# 6-BOOT_SELECT.net
KiCad netlist of a schematic drawn in Altium Designer
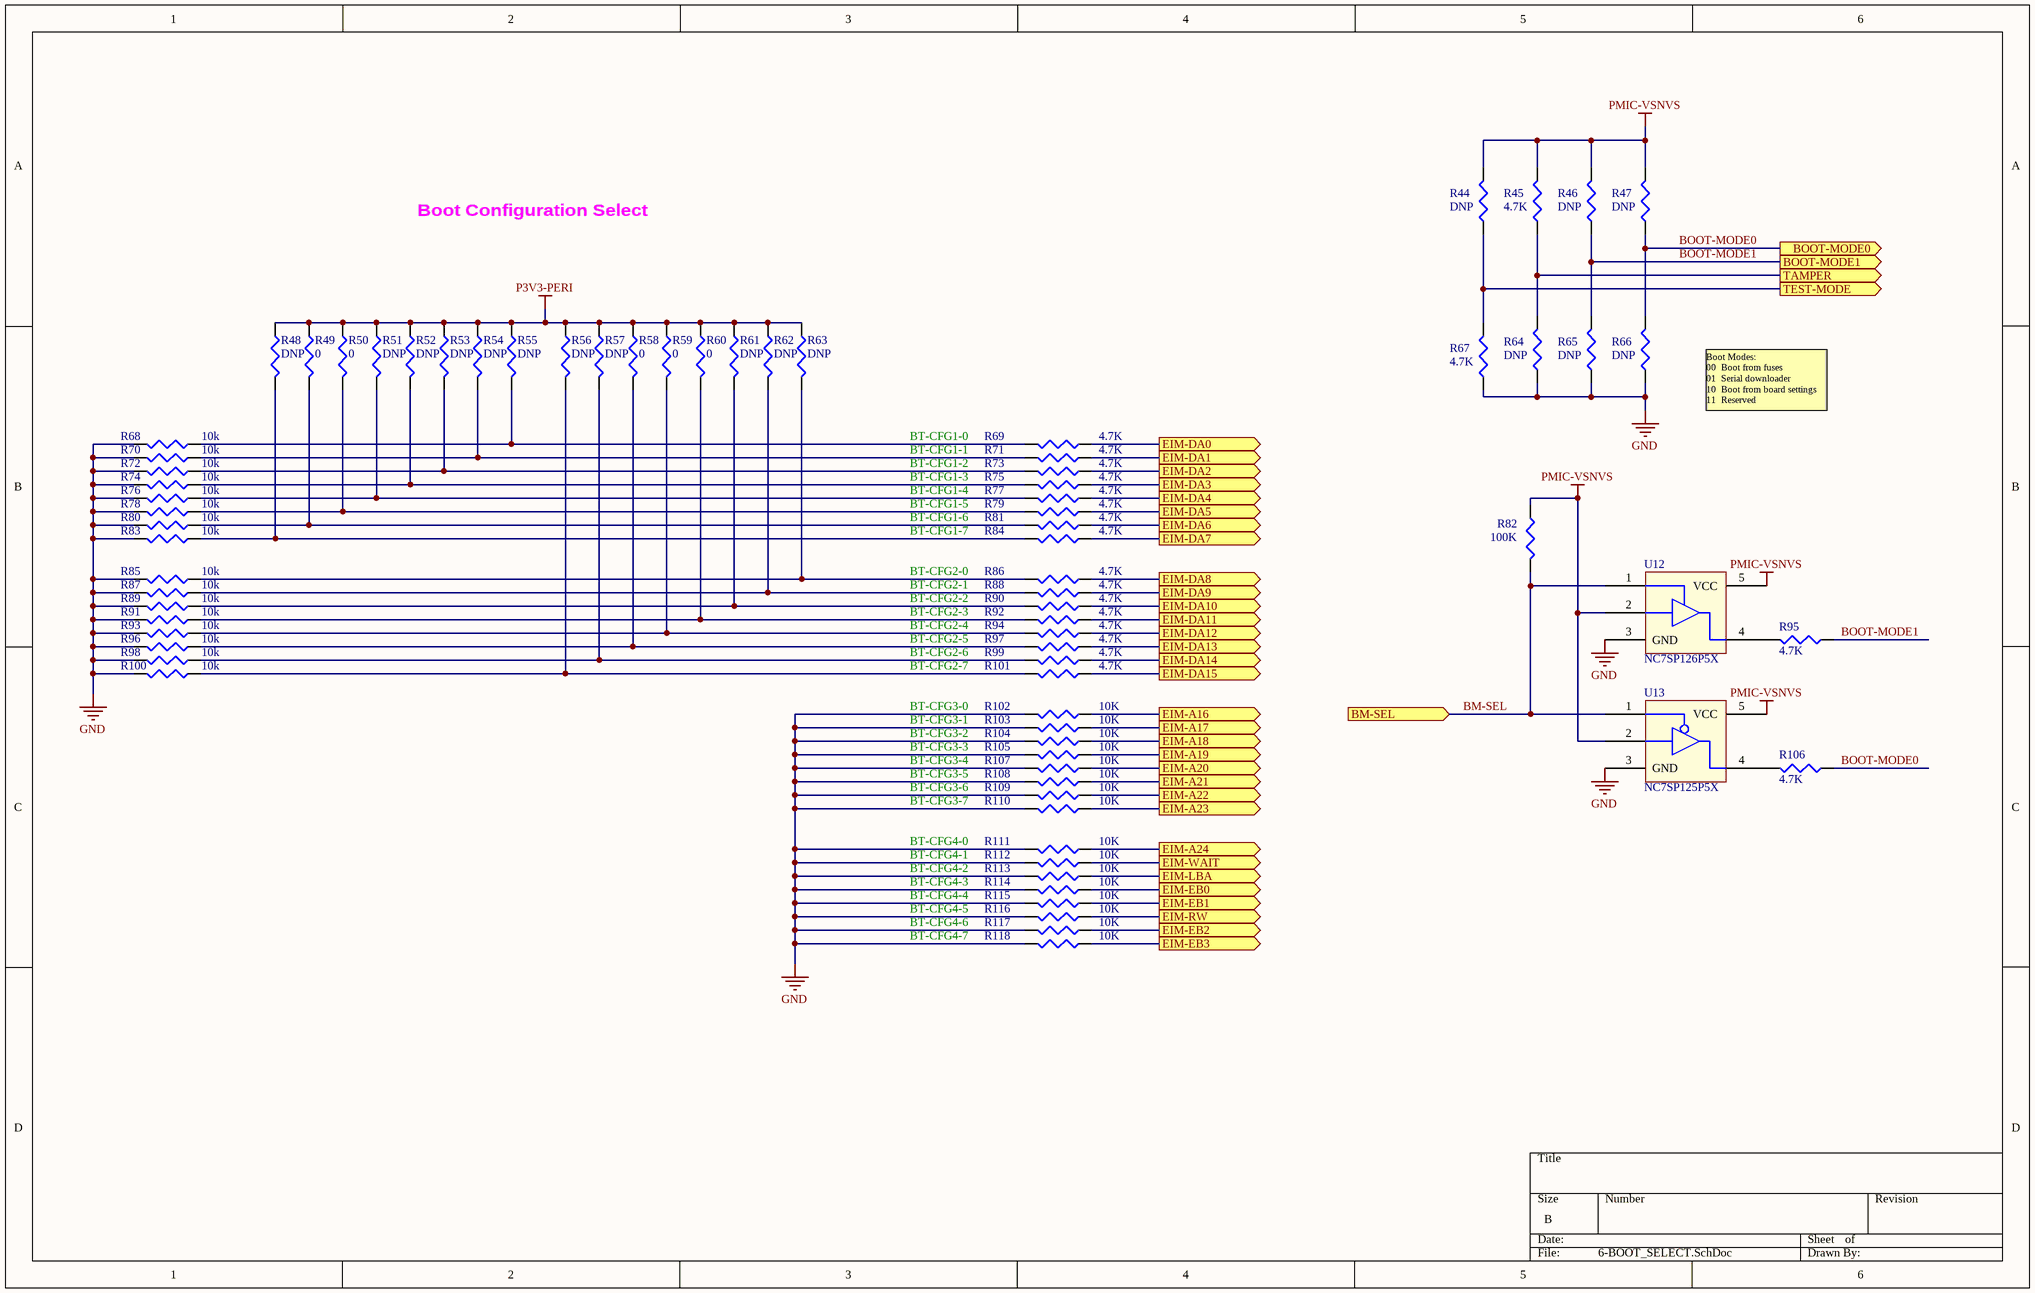
[diagram p0: 6-BOOT_SELECT.SchDoc]

(export (version "E")
  (design (tool "Eeschema 10.0.6"))
  (components
    (comp (ref "R44")
      (value "DNP")
      (footprint "0402_CC")
      (description "Resistor")
      (fields (field (name "PUBLISHER") "Altium Limited"))
      (libsource (lib "Miscellaneous Devices") (part "Res3"))
    )
    (comp (ref "R45")
      (value "4.7K")
      (footprint "0402_CC")
      (description "Resistor")
      (fields (field (name "PUBLISHER") "Altium Limited"))
      (libsource (lib "Miscellaneous Devices") (part "Res3"))
    )
    (comp (ref "R46")
      (value "DNP")
      (footprint "0402_CC")
      (description "Resistor")
      (fields (field (name "PUBLISHER") "Altium Limited"))
      (libsource (lib "Miscellaneous Devices") (part "Res3"))
    )
    (comp (ref "R47")
      (value "DNP")
      (footprint "0402_CC")
      (description "Resistor")
      (fields (field (name "PUBLISHER") "Altium Limited"))
      (libsource (lib "Miscellaneous Devices") (part "Res3"))
    )
    (comp (ref "R48")
      (value "DNP")
      (footprint "0402_CC")
      (description "Resistor")
      (fields (field (name "PUBLISHER") "Altium Limited"))
      (libsource (lib "Miscellaneous Devices") (part "Res3"))
    )
    (comp (ref "R49")
      (value "0")
      (footprint "0402_CC")
      (description "Resistor")
      (fields (field (name "PUBLISHER") "Altium Limited"))
      (libsource (lib "Miscellaneous Devices") (part "Res3"))
    )
    (comp (ref "R50")
      (value "0")
      (footprint "0402_CC")
      (description "Resistor")
      (fields (field (name "PUBLISHER") "Altium Limited"))
      (libsource (lib "Miscellaneous Devices") (part "Res3"))
    )
    (comp (ref "R51")
      (value "DNP")
      (footprint "0402_CC")
      (description "Resistor")
      (fields (field (name "PUBLISHER") "Altium Limited"))
      (libsource (lib "Miscellaneous Devices") (part "Res3"))
    )
    (comp (ref "R52")
      (value "DNP")
      (footprint "0402_CC")
      (description "Resistor")
      (fields (field (name "PUBLISHER") "Altium Limited"))
      (libsource (lib "Miscellaneous Devices") (part "Res3"))
    )
    (comp (ref "R53")
      (value "DNP")
      (footprint "0402_CC")
      (description "Resistor")
      (fields (field (name "PUBLISHER") "Altium Limited"))
      (libsource (lib "Miscellaneous Devices") (part "Res3"))
    )
    (comp (ref "R54")
      (value "DNP")
      (footprint "0402_CC")
      (description "Resistor")
      (fields (field (name "PUBLISHER") "Altium Limited"))
      (libsource (lib "Miscellaneous Devices") (part "Res3"))
    )
    (comp (ref "R55")
      (value "DNP")
      (footprint "0402_CC")
      (description "Resistor")
      (fields (field (name "PUBLISHER") "Altium Limited"))
      (libsource (lib "Miscellaneous Devices") (part "Res3"))
    )
    (comp (ref "R56")
      (value "DNP")
      (footprint "0402_CC")
      (description "Resistor")
      (fields (field (name "PUBLISHER") "Altium Limited"))
      (libsource (lib "Miscellaneous Devices") (part "Res3"))
    )
    (comp (ref "R57")
      (value "DNP")
      (footprint "0402_CC")
      (description "Resistor")
      (fields (field (name "PUBLISHER") "Altium Limited"))
      (libsource (lib "Miscellaneous Devices") (part "Res3"))
    )
    (comp (ref "R58")
      (value "0")
      (footprint "0402_CC")
      (description "Resistor")
      (fields (field (name "PUBLISHER") "Altium Limited"))
      (libsource (lib "Miscellaneous Devices") (part "Res3"))
    )
    (comp (ref "R59")
      (value "0")
      (footprint "0402_CC")
      (description "Resistor")
      (fields (field (name "PUBLISHER") "Altium Limited"))
      (libsource (lib "Miscellaneous Devices") (part "Res3"))
    )
    (comp (ref "R60")
      (value "0")
      (footprint "0402_CC")
      (description "Resistor")
      (fields (field (name "PUBLISHER") "Altium Limited"))
      (libsource (lib "Miscellaneous Devices") (part "Res3"))
    )
    (comp (ref "R61")
      (value "DNP")
      (footprint "0402_CC")
      (description "Resistor")
      (fields (field (name "PUBLISHER") "Altium Limited"))
      (libsource (lib "Miscellaneous Devices") (part "Res3"))
    )
    (comp (ref "R62")
      (value "DNP")
      (footprint "0402_CC")
      (description "Resistor")
      (fields (field (name "PUBLISHER") "Altium Limited"))
      (libsource (lib "Miscellaneous Devices") (part "Res3"))
    )
    (comp (ref "R63")
      (value "DNP")
      (footprint "0402_CC")
      (description "Resistor")
      (fields (field (name "PUBLISHER") "Altium Limited"))
      (libsource (lib "Miscellaneous Devices") (part "Res3"))
    )
    (comp (ref "R64")
      (value "DNP")
      (footprint "0402_CC")
      (description "Resistor")
      (fields (field (name "PUBLISHER") "Altium Limited"))
      (libsource (lib "Miscellaneous Devices") (part "Res3"))
    )
    (comp (ref "R65")
      (value "DNP")
      (footprint "0402_CC")
      (description "Resistor")
      (fields (field (name "PUBLISHER") "Altium Limited"))
      (libsource (lib "Miscellaneous Devices") (part "Res3"))
    )
    (comp (ref "R66")
      (value "DNP")
      (footprint "0402_CC")
      (description "Resistor")
      (fields (field (name "PUBLISHER") "Altium Limited"))
      (libsource (lib "Miscellaneous Devices") (part "Res3"))
    )
    (comp (ref "R67")
      (value "4.7K")
      (footprint "0402_CC")
      (description "Resistor")
      (fields (field (name "PUBLISHER") "Altium Limited"))
      (libsource (lib "Miscellaneous Devices") (part "Res3"))
    )
    (comp (ref "R68")
      (value "10k")
      (footprint "0402_CC")
      (description "Resistor")
      (fields (field (name "PUBLISHER") "Altium Limited"))
      (libsource (lib "Miscellaneous Devices") (part "Res3"))
    )
    (comp (ref "R69")
      (value "4.7K")
      (footprint "0402_CC")
      (description "Resistor")
      (fields (field (name "PUBLISHER") "Altium Limited"))
      (libsource (lib "Miscellaneous Devices") (part "Res3"))
    )
    (comp (ref "R70")
      (value "10k")
      (footprint "0402_CC")
      (description "Resistor")
      (fields (field (name "PUBLISHER") "Altium Limited"))
      (libsource (lib "Miscellaneous Devices") (part "Res3"))
    )
    (comp (ref "R71")
      (value "4.7K")
      (footprint "0402_CC")
      (description "Resistor")
      (fields (field (name "PUBLISHER") "Altium Limited"))
      (libsource (lib "Miscellaneous Devices") (part "Res3"))
    )
    (comp (ref "R72")
      (value "10k")
      (footprint "0402_CC")
      (description "Resistor")
      (fields (field (name "PUBLISHER") "Altium Limited"))
      (libsource (lib "Miscellaneous Devices") (part "Res3"))
    )
    (comp (ref "R73")
      (value "4.7K")
      (footprint "0402_CC")
      (description "Resistor")
      (fields (field (name "PUBLISHER") "Altium Limited"))
      (libsource (lib "Miscellaneous Devices") (part "Res3"))
    )
    (comp (ref "R74")
      (value "10k")
      (footprint "0402_CC")
      (description "Resistor")
      (fields (field (name "PUBLISHER") "Altium Limited"))
      (libsource (lib "Miscellaneous Devices") (part "Res3"))
    )
    (comp (ref "R75")
      (value "4.7K")
      (footprint "0402_CC")
      (description "Resistor")
      (fields (field (name "PUBLISHER") "Altium Limited"))
      (libsource (lib "Miscellaneous Devices") (part "Res3"))
    )
    (comp (ref "R76")
      (value "10k")
      (footprint "0402_CC")
      (description "Resistor")
      (fields (field (name "PUBLISHER") "Altium Limited"))
      (libsource (lib "Miscellaneous Devices") (part "Res3"))
    )
    (comp (ref "R77")
      (value "4.7K")
      (footprint "0402_CC")
      (description "Resistor")
      (fields (field (name "PUBLISHER") "Altium Limited"))
      (libsource (lib "Miscellaneous Devices") (part "Res3"))
    )
    (comp (ref "R78")
      (value "10k")
      (footprint "0402_CC")
      (description "Resistor")
      (fields (field (name "PUBLISHER") "Altium Limited"))
      (libsource (lib "Miscellaneous Devices") (part "Res3"))
    )
    (comp (ref "R79")
      (value "4.7K")
      (footprint "0402_CC")
      (description "Resistor")
      (fields (field (name "PUBLISHER") "Altium Limited"))
      (libsource (lib "Miscellaneous Devices") (part "Res3"))
    )
    (comp (ref "R80")
      (value "10k")
      (footprint "0402_CC")
      (description "Resistor")
      (fields (field (name "PUBLISHER") "Altium Limited"))
      (libsource (lib "Miscellaneous Devices") (part "Res3"))
    )
    (comp (ref "R81")
      (value "4.7K")
      (footprint "0402_CC")
      (description "Resistor")
      (fields (field (name "PUBLISHER") "Altium Limited"))
      (libsource (lib "Miscellaneous Devices") (part "Res3"))
    )
    (comp (ref "R82")
      (value "100K")
      (footprint "0402_CC")
      (description "Resistor")
      (fields (field (name "PUBLISHER") "Altium Limited"))
      (libsource (lib "Miscellaneous Devices") (part "Res3"))
    )
    (comp (ref "R83")
      (value "10k")
      (footprint "0402_CC")
      (description "Resistor")
      (fields (field (name "PUBLISHER") "Altium Limited"))
      (libsource (lib "Miscellaneous Devices") (part "Res3"))
    )
    (comp (ref "R84")
      (value "4.7K")
      (footprint "0402_CC")
      (description "Resistor")
      (fields (field (name "PUBLISHER") "Altium Limited"))
      (libsource (lib "Miscellaneous Devices") (part "Res3"))
    )
    (comp (ref "R85")
      (value "10k")
      (footprint "0402_CC")
      (description "Resistor")
      (fields (field (name "PUBLISHER") "Altium Limited"))
      (libsource (lib "Miscellaneous Devices") (part "Res3"))
    )
    (comp (ref "R86")
      (value "4.7K")
      (footprint "0402_CC")
      (description "Resistor")
      (fields (field (name "PUBLISHER") "Altium Limited"))
      (libsource (lib "Miscellaneous Devices") (part "Res3"))
    )
    (comp (ref "R87")
      (value "10k")
      (footprint "0402_CC")
      (description "Resistor")
      (fields (field (name "PUBLISHER") "Altium Limited"))
      (libsource (lib "Miscellaneous Devices") (part "Res3"))
    )
    (comp (ref "R88")
      (value "4.7K")
      (footprint "0402_CC")
      (description "Resistor")
      (fields (field (name "PUBLISHER") "Altium Limited"))
      (libsource (lib "Miscellaneous Devices") (part "Res3"))
    )
    (comp (ref "R89")
      (value "10k")
      (footprint "0402_CC")
      (description "Resistor")
      (fields (field (name "PUBLISHER") "Altium Limited"))
      (libsource (lib "Miscellaneous Devices") (part "Res3"))
    )
    (comp (ref "R90")
      (value "4.7K")
      (footprint "0402_CC")
      (description "Resistor")
      (fields (field (name "PUBLISHER") "Altium Limited"))
      (libsource (lib "Miscellaneous Devices") (part "Res3"))
    )
    (comp (ref "R91")
      (value "10k")
      (footprint "0402_CC")
      (description "Resistor")
      (fields (field (name "PUBLISHER") "Altium Limited"))
      (libsource (lib "Miscellaneous Devices") (part "Res3"))
    )
    (comp (ref "R92")
      (value "4.7K")
      (footprint "0402_CC")
      (description "Resistor")
      (fields (field (name "PUBLISHER") "Altium Limited"))
      (libsource (lib "Miscellaneous Devices") (part "Res3"))
    )
    (comp (ref "R93")
      (value "10k")
      (footprint "0402_CC")
      (description "Resistor")
      (fields (field (name "PUBLISHER") "Altium Limited"))
      (libsource (lib "Miscellaneous Devices") (part "Res3"))
    )
    (comp (ref "R94")
      (value "4.7K")
      (footprint "0402_CC")
      (description "Resistor")
      (fields (field (name "PUBLISHER") "Altium Limited"))
      (libsource (lib "Miscellaneous Devices") (part "Res3"))
    )
    (comp (ref "R95")
      (value "4.7K")
      (footprint "0402_CC")
      (description "Resistor")
      (fields (field (name "PUBLISHER") "Altium Limited"))
      (libsource (lib "Miscellaneous Devices") (part "Res3"))
    )
    (comp (ref "R96")
      (value "10k")
      (footprint "0402_CC")
      (description "Resistor")
      (fields (field (name "PUBLISHER") "Altium Limited"))
      (libsource (lib "Miscellaneous Devices") (part "Res3"))
    )
    (comp (ref "R97")
      (value "4.7K")
      (footprint "0402_CC")
      (description "Resistor")
      (fields (field (name "PUBLISHER") "Altium Limited"))
      (libsource (lib "Miscellaneous Devices") (part "Res3"))
    )
    (comp (ref "R98")
      (value "10k")
      (footprint "0402_CC")
      (description "Resistor")
      (fields (field (name "PUBLISHER") "Altium Limited"))
      (libsource (lib "Miscellaneous Devices") (part "Res3"))
    )
    (comp (ref "R99")
      (value "4.7K")
      (footprint "0402_CC")
      (description "Resistor")
      (fields (field (name "PUBLISHER") "Altium Limited"))
      (libsource (lib "Miscellaneous Devices") (part "Res3"))
    )
    (comp (ref "R100")
      (value "10k")
      (footprint "0402_CC")
      (description "Resistor")
      (fields (field (name "PUBLISHER") "Altium Limited"))
      (libsource (lib "Miscellaneous Devices") (part "Res3"))
    )
    (comp (ref "R101")
      (value "4.7K")
      (footprint "0402_CC")
      (description "Resistor")
      (fields (field (name "PUBLISHER") "Altium Limited"))
      (libsource (lib "Miscellaneous Devices") (part "Res3"))
    )
    (comp (ref "R102")
      (value "10K")
      (footprint "0402_CC")
      (description "Resistor")
      (fields (field (name "PUBLISHER") "Altium Limited"))
      (libsource (lib "Miscellaneous Devices") (part "Res3"))
    )
    (comp (ref "R103")
      (value "10K")
      (footprint "0402_CC")
      (description "Resistor")
      (fields (field (name "PUBLISHER") "Altium Limited"))
      (libsource (lib "Miscellaneous Devices") (part "Res3"))
    )
    (comp (ref "R104")
      (value "10K")
      (footprint "0402_CC")
      (description "Resistor")
      (fields (field (name "PUBLISHER") "Altium Limited"))
      (libsource (lib "Miscellaneous Devices") (part "Res3"))
    )
    (comp (ref "R105")
      (value "10K")
      (footprint "0402_CC")
      (description "Resistor")
      (fields (field (name "PUBLISHER") "Altium Limited"))
      (libsource (lib "Miscellaneous Devices") (part "Res3"))
    )
    (comp (ref "R106")
      (value "4.7K")
      (footprint "0402_CC")
      (description "Resistor")
      (fields (field (name "PUBLISHER") "Altium Limited"))
      (libsource (lib "Miscellaneous Devices") (part "Res3"))
    )
    (comp (ref "R107")
      (value "10K")
      (footprint "0402_CC")
      (description "Resistor")
      (fields (field (name "PUBLISHER") "Altium Limited"))
      (libsource (lib "Miscellaneous Devices") (part "Res3"))
    )
    (comp (ref "R108")
      (value "10K")
      (footprint "0402_CC")
      (description "Resistor")
      (fields (field (name "PUBLISHER") "Altium Limited"))
      (libsource (lib "Miscellaneous Devices") (part "Res3"))
    )
    (comp (ref "R109")
      (value "10K")
      (footprint "0402_CC")
      (description "Resistor")
      (fields (field (name "PUBLISHER") "Altium Limited"))
      (libsource (lib "Miscellaneous Devices") (part "Res3"))
    )
    (comp (ref "R110")
      (value "10K")
      (footprint "0402_CC")
      (description "Resistor")
      (fields (field (name "PUBLISHER") "Altium Limited"))
      (libsource (lib "Miscellaneous Devices") (part "Res3"))
    )
    (comp (ref "R111")
      (value "10K")
      (footprint "0402_CC")
      (description "Resistor")
      (fields (field (name "PUBLISHER") "Altium Limited"))
      (libsource (lib "Miscellaneous Devices") (part "Res3"))
    )
    (comp (ref "R112")
      (value "10K")
      (footprint "0402_CC")
      (description "Resistor")
      (fields (field (name "PUBLISHER") "Altium Limited"))
      (libsource (lib "Miscellaneous Devices") (part "Res3"))
    )
    (comp (ref "R113")
      (value "10K")
      (footprint "0402_CC")
      (description "Resistor")
      (fields (field (name "PUBLISHER") "Altium Limited"))
      (libsource (lib "Miscellaneous Devices") (part "Res3"))
    )
    (comp (ref "R114")
      (value "10K")
      (footprint "0402_CC")
      (description "Resistor")
      (fields (field (name "PUBLISHER") "Altium Limited"))
      (libsource (lib "Miscellaneous Devices") (part "Res3"))
    )
    (comp (ref "R115")
      (value "10K")
      (footprint "0402_CC")
      (description "Resistor")
      (fields (field (name "PUBLISHER") "Altium Limited"))
      (libsource (lib "Miscellaneous Devices") (part "Res3"))
    )
    (comp (ref "R116")
      (value "10K")
      (footprint "0402_CC")
      (description "Resistor")
      (fields (field (name "PUBLISHER") "Altium Limited"))
      (libsource (lib "Miscellaneous Devices") (part "Res3"))
    )
    (comp (ref "R117")
      (value "10K")
      (footprint "0402_CC")
      (description "Resistor")
      (fields (field (name "PUBLISHER") "Altium Limited"))
      (libsource (lib "Miscellaneous Devices") (part "Res3"))
    )
    (comp (ref "R118")
      (value "10K")
      (footprint "0402_CC")
      (description "Resistor")
      (fields (field (name "PUBLISHER") "Altium Limited"))
      (libsource (lib "Miscellaneous Devices") (part "Res3"))
    )
    (comp (ref "U12")
      (value "NC7SP126P5X")
      (footprint "SC70")
      (libsource (lib "Schlib") (part "NC7SP126P5X"))
    )
    (comp (ref "U13")
      (value "NC7SP125P5X")
      (footprint "SC70")
      (libsource (lib "Schlib") (part "NC7SP125P5X"))
    )
  )
  (nets
    (net (code "1") (name "/BM-SEL") (class "Default")
      (node (ref "R82") (pin "2") (pinfunction "2_2") (pintype "passive"))
      (node (ref "U12") (pin "1") (pinfunction "OE_1") (pintype "passive"))
      (node (ref "U13") (pin "1") (pinfunction "OE_1") (pintype "passive"))
    )
    (net (code "2") (name "/BOOT-MODE0") (class "Default")
      (node (ref "R106") (pin "1") (pinfunction "1_1") (pintype "passive"))
      (node (ref "R47") (pin "1") (pinfunction "1_1") (pintype "passive"))
      (node (ref "R66") (pin "2") (pinfunction "2_2") (pintype "passive"))
    )
    (net (code "3") (name "/BOOT-MODE1") (class "Default")
      (node (ref "R46") (pin "1") (pinfunction "1_1") (pintype "passive"))
      (node (ref "R65") (pin "2") (pinfunction "2_2") (pintype "passive"))
      (node (ref "R95") (pin "1") (pinfunction "1_1") (pintype "passive"))
    )
    (net (code "4") (name "/EIM-A16") (class "Default")
      (node (ref "R102") (pin "1") (pinfunction "1_1") (pintype "passive"))
    )
    (net (code "5") (name "/EIM-A17") (class "Default")
      (node (ref "R103") (pin "1") (pinfunction "1_1") (pintype "passive"))
    )
    (net (code "6") (name "/EIM-A18") (class "Default")
      (node (ref "R104") (pin "1") (pinfunction "1_1") (pintype "passive"))
    )
    (net (code "7") (name "/EIM-A19") (class "Default")
      (node (ref "R105") (pin "1") (pinfunction "1_1") (pintype "passive"))
    )
    (net (code "8") (name "/EIM-A20") (class "Default")
      (node (ref "R107") (pin "1") (pinfunction "1_1") (pintype "passive"))
    )
    (net (code "9") (name "/EIM-A21") (class "Default")
      (node (ref "R108") (pin "1") (pinfunction "1_1") (pintype "passive"))
    )
    (net (code "10") (name "/EIM-A22") (class "Default")
      (node (ref "R109") (pin "1") (pinfunction "1_1") (pintype "passive"))
    )
    (net (code "11") (name "/EIM-A23") (class "Default")
      (node (ref "R110") (pin "1") (pinfunction "1_1") (pintype "passive"))
    )
    (net (code "12") (name "/EIM-A24") (class "Default")
      (node (ref "R111") (pin "1") (pinfunction "1_1") (pintype "passive"))
    )
    (net (code "13") (name "/EIM-DA0") (class "Default")
      (node (ref "R69") (pin "1") (pinfunction "1_1") (pintype "passive"))
    )
    (net (code "14") (name "/EIM-DA1") (class "Default")
      (node (ref "R71") (pin "1") (pinfunction "1_1") (pintype "passive"))
    )
    (net (code "15") (name "/EIM-DA2") (class "Default")
      (node (ref "R73") (pin "1") (pinfunction "1_1") (pintype "passive"))
    )
    (net (code "16") (name "/EIM-DA3") (class "Default")
      (node (ref "R75") (pin "1") (pinfunction "1_1") (pintype "passive"))
    )
    (net (code "17") (name "/EIM-DA4") (class "Default")
      (node (ref "R77") (pin "1") (pinfunction "1_1") (pintype "passive"))
    )
    (net (code "18") (name "/EIM-DA5") (class "Default")
      (node (ref "R79") (pin "1") (pinfunction "1_1") (pintype "passive"))
    )
    (net (code "19") (name "/EIM-DA6") (class "Default")
      (node (ref "R81") (pin "1") (pinfunction "1_1") (pintype "passive"))
    )
    (net (code "20") (name "/EIM-DA7") (class "Default")
      (node (ref "R84") (pin "1") (pinfunction "1_1") (pintype "passive"))
    )
    (net (code "21") (name "/EIM-DA8") (class "Default")
      (node (ref "R86") (pin "1") (pinfunction "1_1") (pintype "passive"))
    )
    (net (code "22") (name "/EIM-DA9") (class "Default")
      (node (ref "R88") (pin "1") (pinfunction "1_1") (pintype "passive"))
    )
    (net (code "23") (name "/EIM-DA10") (class "Default")
      (node (ref "R90") (pin "1") (pinfunction "1_1") (pintype "passive"))
    )
    (net (code "24") (name "/EIM-DA11") (class "Default")
      (node (ref "R92") (pin "1") (pinfunction "1_1") (pintype "passive"))
    )
    (net (code "25") (name "/EIM-DA12") (class "Default")
      (node (ref "R94") (pin "1") (pinfunction "1_1") (pintype "passive"))
    )
    (net (code "26") (name "/EIM-DA13") (class "Default")
      (node (ref "R97") (pin "1") (pinfunction "1_1") (pintype "passive"))
    )
    (net (code "27") (name "/EIM-DA14") (class "Default")
      (node (ref "R99") (pin "1") (pinfunction "1_1") (pintype "passive"))
    )
    (net (code "28") (name "/EIM-DA15") (class "Default")
      (node (ref "R101") (pin "1") (pinfunction "1_1") (pintype "passive"))
    )
    (net (code "29") (name "/EIM-EB0") (class "Default")
      (node (ref "R114") (pin "1") (pinfunction "1_1") (pintype "passive"))
    )
    (net (code "30") (name "/EIM-EB1") (class "Default")
      (node (ref "R115") (pin "1") (pinfunction "1_1") (pintype "passive"))
    )
    (net (code "31") (name "/EIM-EB2") (class "Default")
      (node (ref "R117") (pin "1") (pinfunction "1_1") (pintype "passive"))
    )
    (net (code "32") (name "/EIM-EB3") (class "Default")
      (node (ref "R118") (pin "1") (pinfunction "1_1") (pintype "passive"))
    )
    (net (code "33") (name "/EIM-LBA") (class "Default")
      (node (ref "R113") (pin "1") (pinfunction "1_1") (pintype "passive"))
    )
    (net (code "34") (name "/EIM-RW") (class "Default")
      (node (ref "R116") (pin "1") (pinfunction "1_1") (pintype "passive"))
    )
    (net (code "35") (name "/EIM-WAIT") (class "Default")
      (node (ref "R112") (pin "1") (pinfunction "1_1") (pintype "passive"))
    )
    (net (code "36") (name "/TAMPER") (class "Default")
      (node (ref "R45") (pin "1") (pinfunction "1_1") (pintype "passive"))
      (node (ref "R64") (pin "2") (pinfunction "2_2") (pintype "passive"))
    )
    (net (code "37") (name "/TEST-MODE") (class "Default")
      (node (ref "R44") (pin "1") (pinfunction "1_1") (pintype "passive"))
      (node (ref "R67") (pin "2") (pinfunction "2_2") (pintype "passive"))
    )
    (net (code "38") (name "GND") (class "Default")
      (node (ref "R100") (pin "2") (pinfunction "2_2") (pintype "passive"))
      (node (ref "R102") (pin "2") (pinfunction "2_2") (pintype "passive"))
      (node (ref "R103") (pin "2") (pinfunction "2_2") (pintype "passive"))
      (node (ref "R104") (pin "2") (pinfunction "2_2") (pintype "passive"))
      (node (ref "R105") (pin "2") (pinfunction "2_2") (pintype "passive"))
      (node (ref "R107") (pin "2") (pinfunction "2_2") (pintype "passive"))
      (node (ref "R108") (pin "2") (pinfunction "2_2") (pintype "passive"))
      (node (ref "R109") (pin "2") (pinfunction "2_2") (pintype "passive"))
      (node (ref "R110") (pin "2") (pinfunction "2_2") (pintype "passive"))
      (node (ref "R111") (pin "2") (pinfunction "2_2") (pintype "passive"))
      (node (ref "R112") (pin "2") (pinfunction "2_2") (pintype "passive"))
      (node (ref "R113") (pin "2") (pinfunction "2_2") (pintype "passive"))
      (node (ref "R114") (pin "2") (pinfunction "2_2") (pintype "passive"))
      (node (ref "R115") (pin "2") (pinfunction "2_2") (pintype "passive"))
      (node (ref "R116") (pin "2") (pinfunction "2_2") (pintype "passive"))
      (node (ref "R117") (pin "2") (pinfunction "2_2") (pintype "passive"))
      (node (ref "R118") (pin "2") (pinfunction "2_2") (pintype "passive"))
      (node (ref "R64") (pin "1") (pinfunction "1_1") (pintype "passive"))
      (node (ref "R65") (pin "1") (pinfunction "1_1") (pintype "passive"))
      (node (ref "R66") (pin "1") (pinfunction "1_1") (pintype "passive"))
      (node (ref "R67") (pin "1") (pinfunction "1_1") (pintype "passive"))
      (node (ref "R68") (pin "2") (pinfunction "2_2") (pintype "passive"))
      (node (ref "R70") (pin "2") (pinfunction "2_2") (pintype "passive"))
      (node (ref "R72") (pin "2") (pinfunction "2_2") (pintype "passive"))
      (node (ref "R74") (pin "2") (pinfunction "2_2") (pintype "passive"))
      (node (ref "R76") (pin "2") (pinfunction "2_2") (pintype "passive"))
      (node (ref "R78") (pin "2") (pinfunction "2_2") (pintype "passive"))
      (node (ref "R80") (pin "2") (pinfunction "2_2") (pintype "passive"))
      (node (ref "R83") (pin "2") (pinfunction "2_2") (pintype "passive"))
      (node (ref "R85") (pin "2") (pinfunction "2_2") (pintype "passive"))
      (node (ref "R87") (pin "2") (pinfunction "2_2") (pintype "passive"))
      (node (ref "R89") (pin "2") (pinfunction "2_2") (pintype "passive"))
      (node (ref "R91") (pin "2") (pinfunction "2_2") (pintype "passive"))
      (node (ref "R93") (pin "2") (pinfunction "2_2") (pintype "passive"))
      (node (ref "R96") (pin "2") (pinfunction "2_2") (pintype "passive"))
      (node (ref "R98") (pin "2") (pinfunction "2_2") (pintype "passive"))
      (node (ref "U12") (pin "3") (pinfunction "GND_3") (pintype "passive"))
      (node (ref "U13") (pin "3") (pinfunction "GND_3") (pintype "passive"))
    )
    (net (code "39") (name "Net-(R48-Pad2)") (class "Default")
      (node (ref "R48") (pin "2") (pinfunction "2_2") (pintype "passive"))
      (node (ref "R83") (pin "1") (pinfunction "1_1") (pintype "passive"))
      (node (ref "R84") (pin "2") (pinfunction "2_2") (pintype "passive"))
    )
    (net (code "40") (name "Net-(R49-Pad2)") (class "Default")
      (node (ref "R49") (pin "2") (pinfunction "2_2") (pintype "passive"))
      (node (ref "R80") (pin "1") (pinfunction "1_1") (pintype "passive"))
      (node (ref "R81") (pin "2") (pinfunction "2_2") (pintype "passive"))
    )
    (net (code "41") (name "Net-(R50-Pad2)") (class "Default")
      (node (ref "R50") (pin "2") (pinfunction "2_2") (pintype "passive"))
      (node (ref "R78") (pin "1") (pinfunction "1_1") (pintype "passive"))
      (node (ref "R79") (pin "2") (pinfunction "2_2") (pintype "passive"))
    )
    (net (code "42") (name "Net-(R51-Pad2)") (class "Default")
      (node (ref "R51") (pin "2") (pinfunction "2_2") (pintype "passive"))
      (node (ref "R76") (pin "1") (pinfunction "1_1") (pintype "passive"))
      (node (ref "R77") (pin "2") (pinfunction "2_2") (pintype "passive"))
    )
    (net (code "43") (name "Net-(R52-Pad2)") (class "Default")
      (node (ref "R52") (pin "2") (pinfunction "2_2") (pintype "passive"))
      (node (ref "R74") (pin "1") (pinfunction "1_1") (pintype "passive"))
      (node (ref "R75") (pin "2") (pinfunction "2_2") (pintype "passive"))
    )
    (net (code "44") (name "Net-(R53-Pad2)") (class "Default")
      (node (ref "R53") (pin "2") (pinfunction "2_2") (pintype "passive"))
      (node (ref "R72") (pin "1") (pinfunction "1_1") (pintype "passive"))
      (node (ref "R73") (pin "2") (pinfunction "2_2") (pintype "passive"))
    )
    (net (code "45") (name "Net-(R54-Pad2)") (class "Default")
      (node (ref "R54") (pin "2") (pinfunction "2_2") (pintype "passive"))
      (node (ref "R70") (pin "1") (pinfunction "1_1") (pintype "passive"))
      (node (ref "R71") (pin "2") (pinfunction "2_2") (pintype "passive"))
    )
    (net (code "46") (name "Net-(R55-Pad2)") (class "Default")
      (node (ref "R55") (pin "2") (pinfunction "2_2") (pintype "passive"))
      (node (ref "R68") (pin "1") (pinfunction "1_1") (pintype "passive"))
      (node (ref "R69") (pin "2") (pinfunction "2_2") (pintype "passive"))
    )
    (net (code "47") (name "Net-(R57-Pad2)") (class "Default")
      (node (ref "R57") (pin "2") (pinfunction "2_2") (pintype "passive"))
      (node (ref "R98") (pin "1") (pinfunction "1_1") (pintype "passive"))
      (node (ref "R99") (pin "2") (pinfunction "2_2") (pintype "passive"))
    )
    (net (code "48") (name "Net-(R58-Pad2)") (class "Default")
      (node (ref "R58") (pin "2") (pinfunction "2_2") (pintype "passive"))
      (node (ref "R96") (pin "1") (pinfunction "1_1") (pintype "passive"))
      (node (ref "R97") (pin "2") (pinfunction "2_2") (pintype "passive"))
    )
    (net (code "49") (name "Net-(R59-Pad2)") (class "Default")
      (node (ref "R59") (pin "2") (pinfunction "2_2") (pintype "passive"))
      (node (ref "R93") (pin "1") (pinfunction "1_1") (pintype "passive"))
      (node (ref "R94") (pin "2") (pinfunction "2_2") (pintype "passive"))
    )
    (net (code "50") (name "Net-(R60-Pad2)") (class "Default")
      (node (ref "R60") (pin "2") (pinfunction "2_2") (pintype "passive"))
      (node (ref "R91") (pin "1") (pinfunction "1_1") (pintype "passive"))
      (node (ref "R92") (pin "2") (pinfunction "2_2") (pintype "passive"))
    )
    (net (code "51") (name "Net-(R61-Pad2)") (class "Default")
      (node (ref "R61") (pin "2") (pinfunction "2_2") (pintype "passive"))
      (node (ref "R89") (pin "1") (pinfunction "1_1") (pintype "passive"))
      (node (ref "R90") (pin "2") (pinfunction "2_2") (pintype "passive"))
    )
    (net (code "52") (name "Net-(R62-Pad2)") (class "Default")
      (node (ref "R62") (pin "2") (pinfunction "2_2") (pintype "passive"))
      (node (ref "R87") (pin "1") (pinfunction "1_1") (pintype "passive"))
      (node (ref "R88") (pin "2") (pinfunction "2_2") (pintype "passive"))
    )
    (net (code "53") (name "Net-(R63-Pad2)") (class "Default")
      (node (ref "R63") (pin "2") (pinfunction "2_2") (pintype "passive"))
      (node (ref "R85") (pin "1") (pinfunction "1_1") (pintype "passive"))
      (node (ref "R86") (pin "2") (pinfunction "2_2") (pintype "passive"))
    )
    (net (code "54") (name "Net-(R100-Pad1)") (class "Default")
      (node (ref "R100") (pin "1") (pinfunction "1_1") (pintype "passive"))
      (node (ref "R101") (pin "2") (pinfunction "2_2") (pintype "passive"))
      (node (ref "R56") (pin "2") (pinfunction "2_2") (pintype "passive"))
    )
    (net (code "55") (name "Net-(U12-Y)") (class "Default")
      (node (ref "R95") (pin "2") (pinfunction "2_2") (pintype "passive"))
      (node (ref "U12") (pin "4") (pinfunction "Y_4") (pintype "passive"))
    )
    (net (code "56") (name "Net-(U13-Y)") (class "Default")
      (node (ref "R106") (pin "2") (pinfunction "2_2") (pintype "passive"))
      (node (ref "U13") (pin "4") (pinfunction "Y_4") (pintype "passive"))
    )
    (net (code "57") (name "P3V3-PERI") (class "Default")
      (node (ref "R48") (pin "1") (pinfunction "1_1") (pintype "passive"))
      (node (ref "R49") (pin "1") (pinfunction "1_1") (pintype "passive"))
      (node (ref "R50") (pin "1") (pinfunction "1_1") (pintype "passive"))
      (node (ref "R51") (pin "1") (pinfunction "1_1") (pintype "passive"))
      (node (ref "R52") (pin "1") (pinfunction "1_1") (pintype "passive"))
      (node (ref "R53") (pin "1") (pinfunction "1_1") (pintype "passive"))
      (node (ref "R54") (pin "1") (pinfunction "1_1") (pintype "passive"))
      (node (ref "R55") (pin "1") (pinfunction "1_1") (pintype "passive"))
      (node (ref "R56") (pin "1") (pinfunction "1_1") (pintype "passive"))
      (node (ref "R57") (pin "1") (pinfunction "1_1") (pintype "passive"))
      (node (ref "R58") (pin "1") (pinfunction "1_1") (pintype "passive"))
      (node (ref "R59") (pin "1") (pinfunction "1_1") (pintype "passive"))
      (node (ref "R60") (pin "1") (pinfunction "1_1") (pintype "passive"))
      (node (ref "R61") (pin "1") (pinfunction "1_1") (pintype "passive"))
      (node (ref "R62") (pin "1") (pinfunction "1_1") (pintype "passive"))
      (node (ref "R63") (pin "1") (pinfunction "1_1") (pintype "passive"))
    )
    (net (code "58") (name "PMIC-VSNVS") (class "Default")
      (node (ref "R44") (pin "2") (pinfunction "2_2") (pintype "passive"))
      (node (ref "R45") (pin "2") (pinfunction "2_2") (pintype "passive"))
      (node (ref "R46") (pin "2") (pinfunction "2_2") (pintype "passive"))
      (node (ref "R47") (pin "2") (pinfunction "2_2") (pintype "passive"))
      (node (ref "R82") (pin "1") (pinfunction "1_1") (pintype "passive"))
      (node (ref "U12") (pin "2") (pinfunction "A_2") (pintype "passive"))
      (node (ref "U12") (pin "5") (pinfunction "VCC_5") (pintype "passive"))
      (node (ref "U13") (pin "2") (pinfunction "A_2") (pintype "passive"))
      (node (ref "U13") (pin "5") (pinfunction "VCC_5") (pintype "passive"))
    )
  )
)
